# RT723.net
KiCad netlist of a schematic drawn in Altium Designer
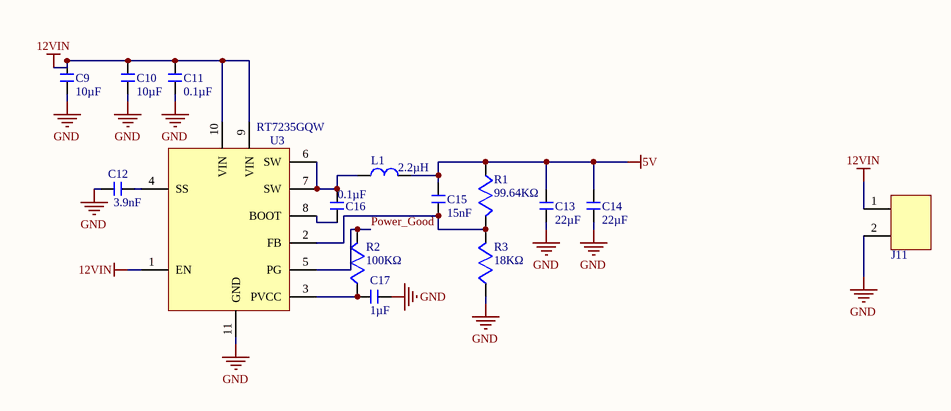
[diagram p0: RT723.SchDoc]

(export (version "E")
  (design (tool "Eeschema 10.0.6"))
  (components
    (comp (ref "C9")
      (value "10µF")
      (footprint "603 CAPACITOR")
      (description "CON SMD 0603")
      (fields (field (name "MPN") "GRM188R61E106MA73D") (field (name "Comment") "0603 CAPACİTOR"))
      (libsource (lib "Schlib1") (part "CON SMD 0603"))
    )
    (comp (ref "C10")
      (value "10µF")
      (footprint "603 CAPACITOR")
      (description "CON SMD 0603")
      (fields (field (name "MPN") "GRM188R61E106MA73D") (field (name "Comment") "0603 CAPACİTOR"))
      (libsource (lib "Schlib1") (part "CON SMD 0603"))
    )
    (comp (ref "C11")
      (value "0.1µF")
      (footprint "402 capacitor - duplicate")
      (description "CAP SMD 402")
      (fields (field (name "MPN") "CL05A104KA5NNNC") (field (name "Comment") "0402 capacitor"))
      (libsource (lib "Schlib1") (part "CAP SMD 402"))
    )
    (comp (ref "C12")
      (value "3.9nF")
      (footprint "402 capacitor - duplicate")
      (description "CAP SMD 402")
      (fields (field (name "MPN") "C0603C392J3GACTU") (field (name "Comment") "0402 capacitor"))
      (libsource (lib "Schlib1") (part "CAP SMD 402"))
    )
    (comp (ref "C13")
      (value "22µF")
      (footprint "805 Capacitor - duplicate")
      (description "CAP SMD 0805")
      (fields (field (name "MPN") "CL10A226MO7JZNC") (field (name "Comment") "0805 capacitor"))
      (libsource (lib "Schlib1") (part "CAP SMD 0805"))
    )
    (comp (ref "C14")
      (value "22µF")
      (footprint "805 Capacitor - duplicate")
      (description "CAP SMD 0805")
      (fields (field (name "MPN") "CL10A226MO7JZNC") (field (name "Comment") "0805 capacitor"))
      (libsource (lib "Schlib1") (part "CAP SMD 0805"))
    )
    (comp (ref "C15")
      (value "15nF")
      (footprint "402 capacitor - duplicate")
      (description "CAP SMD 402")
      (fields (field (name "MPN") "C0402C153J5RECTU") (field (name "Comment") "0402 capacitor"))
      (libsource (lib "Schlib1") (part "CAP SMD 402"))
    )
    (comp (ref "C16")
      (value "0.1µF")
      (footprint "402 capacitor - duplicate")
      (description "CAP SMD 402")
      (fields (field (name "MPN") "CL05A104KA5NNNC") (field (name "Comment") "0402 capacitor"))
      (libsource (lib "Schlib1") (part "CAP SMD 402"))
    )
    (comp (ref "C17")
      (value "1µF")
      (footprint "402 capacitor - duplicate")
      (description "CAP SMD 402")
      (fields (field (name "MPN") "GRM155R6YA105KE11D") (field (name "Comment") "0402 capacitor"))
      (libsource (lib "Schlib1") (part "CAP SMD 402"))
    )
    (comp (ref "J11")
      (value "0901362102")
      (footprint "0901362102")
      (description "CONN HEADER R/A 2POS 2.54MM")
      (libsource (lib "Schlib1") (part "0901362102"))
    )
    (comp (ref "L1")
      (value "2.2µH")
      (footprint "INDUCTOR_2")
      (description "FIXED IND 2.2UH 850MA 175.5 MOHM")
      (fields (field (name "MPN") "BRL2518T2R2M"))
      (libsource (lib "Schlib1") (part "BRL2518T2R2M"))
    )
    (comp (ref "R1")
      (value "99.64KΩ")
      (footprint "402 RESISTOR")
      (description "RES SMD 0402")
      (fields (field (name "Comment") "0402. RESİSTOR"))
      (libsource (lib "Schlib1") (part "RES SMD 0402"))
    )
    (comp (ref "R2")
      (value "100KΩ")
      (footprint "402 RESISTOR")
      (description "RES SMD 0402")
      (fields (field (name "MPN") "ERJ-2RKF1003X") (field (name "Comment") "0402. RESİSTOR"))
      (libsource (lib "Schlib1") (part "RES SMD 0402"))
    )
    (comp (ref "R3")
      (value "18KΩ")
      (footprint "402 RESISTOR")
      (description "RES SMD 0402")
      (fields (field (name "MPN") "ERA-2AEB183X") (field (name "Comment") "0402. RESİSTOR"))
      (libsource (lib "Schlib1") (part "RES SMD 0402"))
    )
    (comp (ref "U3")
      (value "RT7235GQW")
      (footprint "RT7235GQW")
      (description "IC REG BUCK ADJ 5A 10WDFN")
      (libsource (lib "Schlib1") (part "RT7235GQW"))
    )
  )
  (nets
    (net (code "1") (name "/Power_Good") (class "Default")
      (node (ref "R2") (pin "2") (pintype "passive"))
      (node (ref "U3") (pin "5") (pinfunction "PG_5") (pintype "passive"))
    )
    (net (code "2") (name "5V") (class "Default")
      (node (ref "C13") (pin "2") (pintype "passive"))
      (node (ref "C14") (pin "2") (pintype "passive"))
      (node (ref "C15") (pin "1") (pintype "passive"))
      (node (ref "L1") (pin "2") (pintype "passive"))
      (node (ref "R1") (pin "1") (pintype "passive"))
    )
    (net (code "3") (name "12VIN") (class "Default")
      (node (ref "C10") (pin "2") (pintype "passive"))
      (node (ref "C11") (pin "2") (pintype "passive"))
      (node (ref "C9") (pin "2") (pintype "passive"))
      (node (ref "J11") (pin "1") (pintype "passive"))
      (node (ref "U3") (pin "1") (pinfunction "EN_1") (pintype "passive"))
      (node (ref "U3") (pin "10") (pinfunction "VIN_10") (pintype "passive"))
      (node (ref "U3") (pin "9") (pinfunction "VIN_9") (pintype "passive"))
    )
    (net (code "4") (name "GND") (class "Default")
      (node (ref "C10") (pin "1") (pintype "passive"))
      (node (ref "C11") (pin "1") (pintype "passive"))
      (node (ref "C12") (pin "2") (pintype "passive"))
      (node (ref "C13") (pin "1") (pintype "passive"))
      (node (ref "C14") (pin "1") (pintype "passive"))
      (node (ref "C17") (pin "2") (pintype "passive"))
      (node (ref "C9") (pin "1") (pintype "passive"))
      (node (ref "J11") (pin "2") (pintype "passive"))
      (node (ref "R3") (pin "1") (pintype "passive"))
      (node (ref "U3") (pin "11") (pinfunction "GND_11") (pintype "passive"))
    )
    (net (code "5") (name "Net-(C16-Pad1)") (class "Default")
      (node (ref "C16") (pin "1") (pintype "passive"))
      (node (ref "L1") (pin "1") (pintype "passive"))
      (node (ref "U3") (pin "6") (pinfunction "SW_6") (pintype "passive"))
      (node (ref "U3") (pin "7") (pinfunction "SW_7") (pintype "passive"))
    )
    (net (code "6") (name "Net-(U3-BOOT)") (class "Default")
      (node (ref "C16") (pin "2") (pintype "passive"))
      (node (ref "U3") (pin "8") (pinfunction "BOOT_8") (pintype "passive"))
    )
    (net (code "7") (name "Net-(U3-FB)") (class "Default")
      (node (ref "C15") (pin "2") (pintype "passive"))
      (node (ref "R1") (pin "2") (pintype "passive"))
      (node (ref "R3") (pin "2") (pintype "passive"))
      (node (ref "U3") (pin "2") (pinfunction "FB_2") (pintype "passive"))
    )
    (net (code "8") (name "Net-(U3-PVCC)") (class "Default")
      (node (ref "C17") (pin "1") (pintype "passive"))
      (node (ref "R2") (pin "1") (pintype "passive"))
      (node (ref "U3") (pin "3") (pinfunction "PVCC_3") (pintype "passive"))
    )
    (net (code "9") (name "Net-(U3-SS)") (class "Default")
      (node (ref "C12") (pin "1") (pintype "passive"))
      (node (ref "U3") (pin "4") (pinfunction "SS_4") (pintype "passive"))
    )
  )
)
